# SPI_Flash.net
KiCad netlist of a schematic drawn in Altium Designer
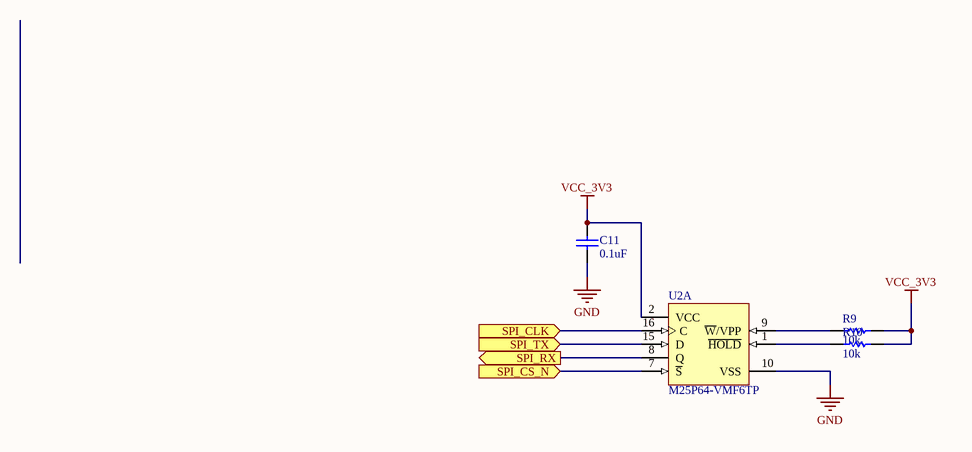
[diagram p0: SPI_Flash.SchDoc]

(export (version "E")
  (design (tool "Eeschema 10.0.6"))
  (components
    (comp (ref "C11")
      (value "0.1uF")
      (footprint "0805_C_S")
      (description "Capacitor")
      (fields (field (name "PUBLISHER") "Altium Limited"))
      (libsource (lib "Miscellaneous Devices") (part "Cap"))
    )
    (comp (ref "R9")
      (value "10k")
      (footprint "0805_R_S")
      (description "Resistor")
      (fields (field (name "PUBLISHER") "Altium Limited"))
      (libsource (lib "Miscellaneous Devices") (part "Res1"))
    )
    (comp (ref "R10")
      (value "10k")
      (footprint "0805_R_S")
      (description "Resistor")
      (fields (field (name "PUBLISHER") "Altium Limited"))
      (libsource (lib "Miscellaneous Devices") (part "Res1"))
    )
    (comp (ref "U2")
      (value "M25P64-VMF6TP")
      (footprint "MICT-MF-16_N")
      (description "64 Mb (x1) Serial NOR Flash Memory, 75 MHz, 2.7 to 3.6 V, 16-pin SO16 Wide (MF), Tape & Reel")
      (fields (field (name "VOLTAGE") "2.7V-3.6VÂ") (field (name "MANUFACTURER") "Micron"))
      (libsource (lib "Altium Content Vault") (part "MICT-M25P64-VMF-16"))
    )
  )
  (nets
    (net (code "1") (name "/SPI_CLK") (class "Default")
      (node (ref "U2") (pin "16") (pinfunction "C_16") (pintype "input"))
    )
    (net (code "2") (name "/SPI_CS_N") (class "Default")
      (node (ref "U2") (pin "7") (pinfunction "~{S}_7") (pintype "input"))
    )
    (net (code "3") (name "/SPI_RX") (class "Default")
      (node (ref "U2") (pin "8") (pinfunction "Q_8") (pintype "tri_state"))
    )
    (net (code "4") (name "/SPI_TX") (class "Default")
      (node (ref "U2") (pin "15") (pinfunction "D_15") (pintype "input"))
    )
    (net (code "5") (name "GND") (class "Default")
      (node (ref "C11") (pin "1") (pinfunction "1_1") (pintype "passive"))
      (node (ref "U2") (pin "10") (pinfunction "VSS_10") (pintype "power_in"))
    )
    (net (code "6") (name "Net-(U2A-~{HOLD})") (class "Default")
      (node (ref "R10") (pin "2") (pinfunction "2_2") (pintype "passive"))
      (node (ref "U2") (pin "1") (pinfunction "~{HOLD}_1") (pintype "input"))
    )
    (net (code "7") (name "Net-(U2A-~{W}{slash}VPP)") (class "Default")
      (node (ref "R9") (pin "2") (pinfunction "2_2") (pintype "passive"))
      (node (ref "U2") (pin "9") (pinfunction "~{W}/VPP_9") (pintype "input"))
    )
    (net (code "8") (name "VCC_3V3") (class "Default")
      (node (ref "C11") (pin "2") (pinfunction "2_2") (pintype "passive"))
      (node (ref "R10") (pin "1") (pinfunction "1_1") (pintype "passive"))
      (node (ref "R9") (pin "1") (pinfunction "1_1") (pintype "passive"))
      (node (ref "U2") (pin "2") (pinfunction "VCC_2") (pintype "power_in"))
    )
  )
)
